# 130801_AriloRX_0_1.net
KiCad netlist of a schematic drawn in EAGLE
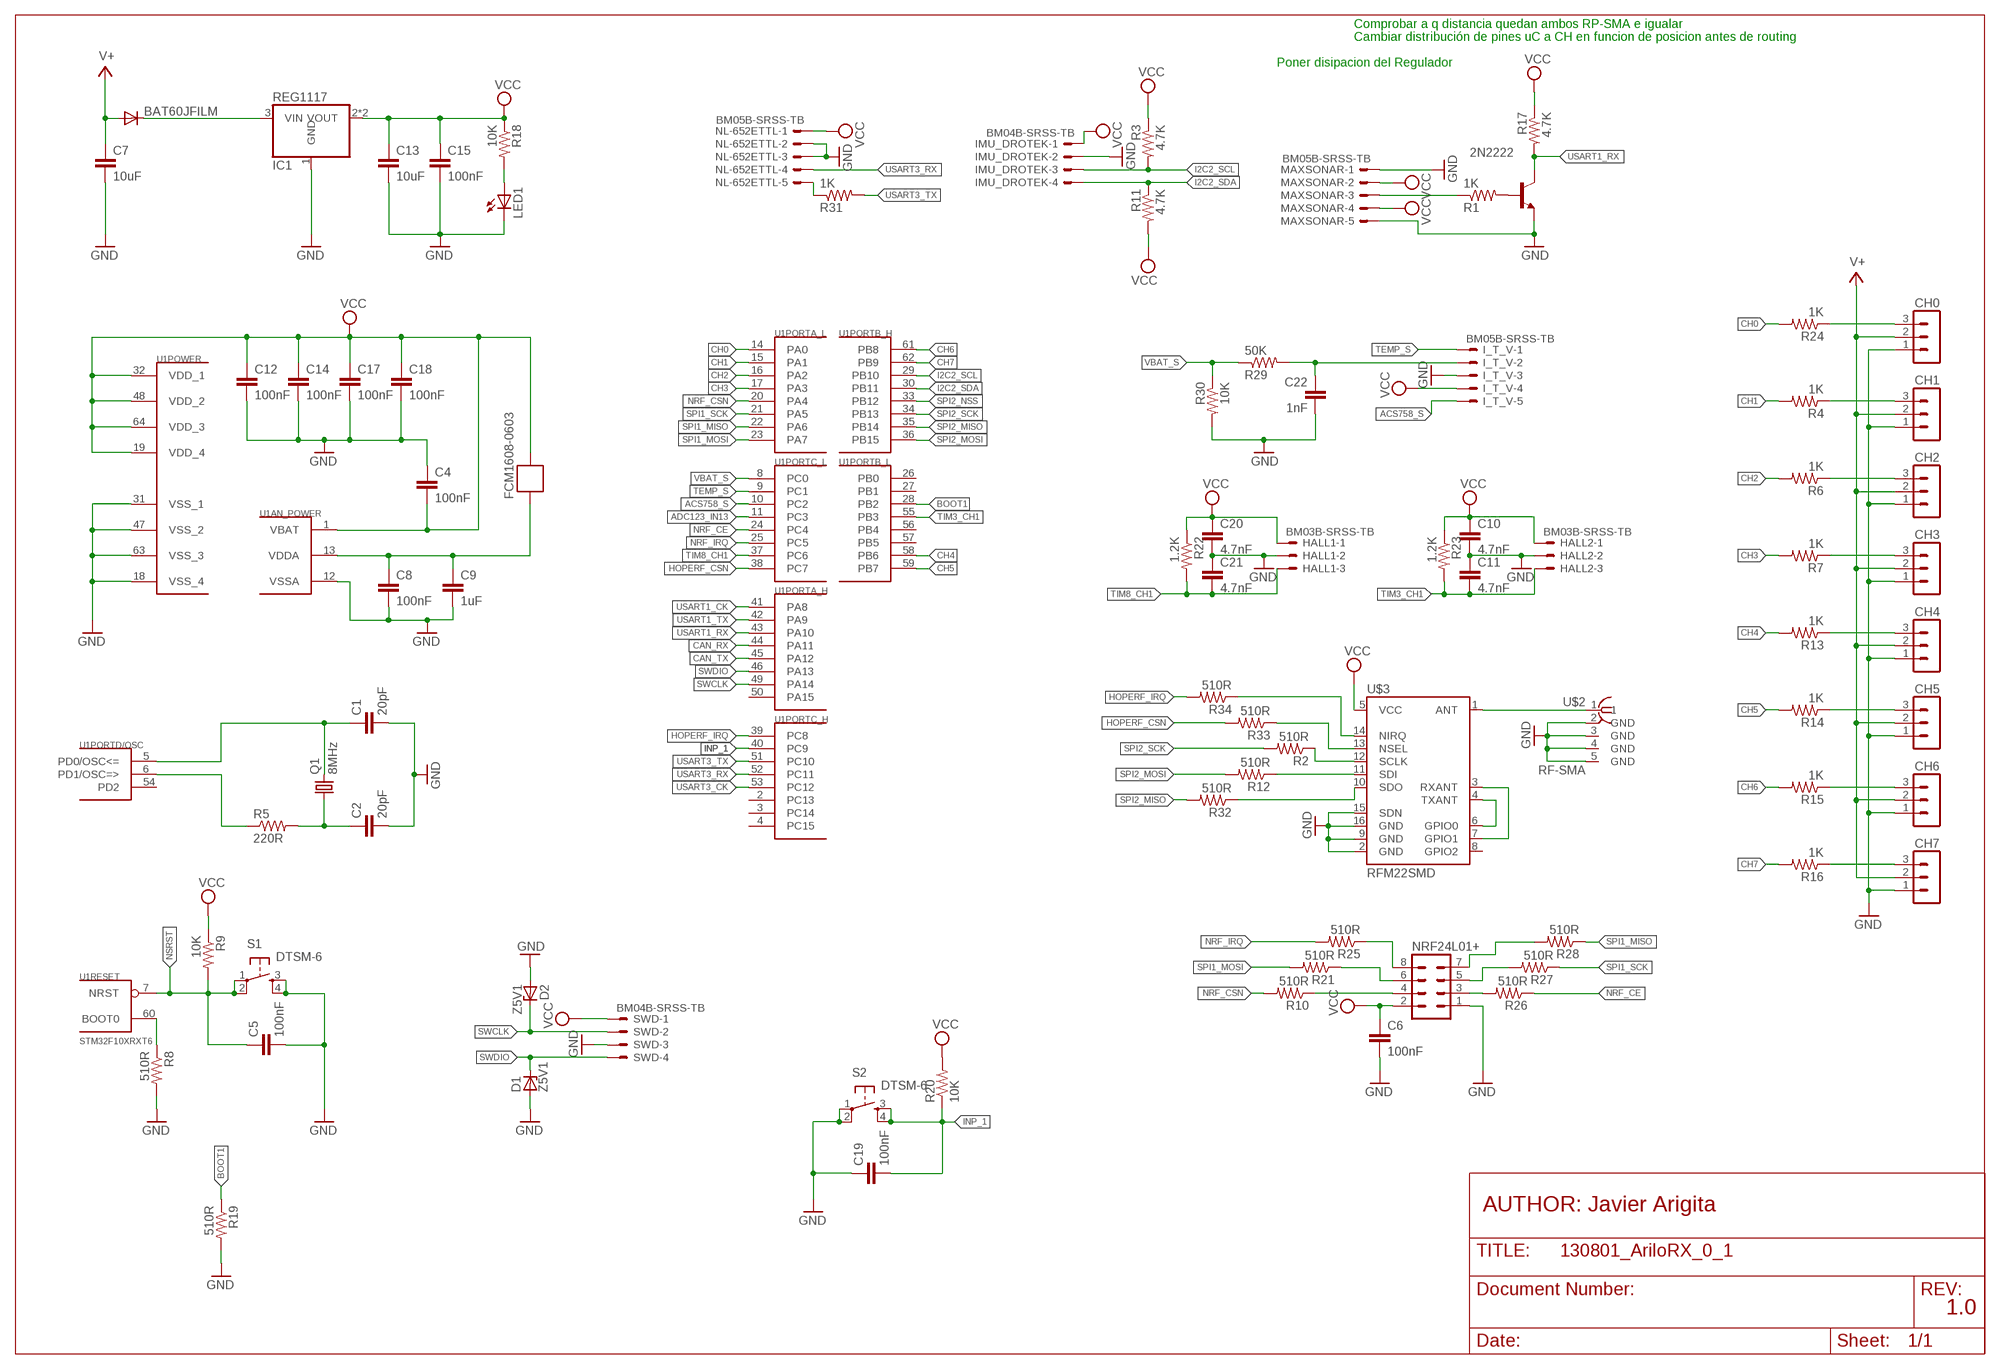
[diagram p0: schematic, sheet 1]

(export (version "E")
  (design (tool "Eeschema 10.0.6"))
  (components
    (comp (ref "2N2222")
      (value "MMBT2222ALT1-NPN-SOT23-BEC")
      (footprint "eagle-import:SOT23-BEC")
      (libsource (lib "eagle-import") (part "-NPN-SOT23-BECMMBT2222ALT1"))
    )
    (comp (ref "BAT60JFILM")
      (value "DIODE-SOD323-R")
      (footprint "eagle-import:SOD323-R")
      (libsource (lib "eagle-import") (part "DIODE-SOD323-R"))
    )
    (comp (ref "C1")
      (value "20pF")
      (footprint "eagle-import:C0805")
      (libsource (lib "eagle-import") (part "C-EUC0805"))
    )
    (comp (ref "C2")
      (value "20pF")
      (footprint "eagle-import:C0805")
      (libsource (lib "eagle-import") (part "C-EUC0805"))
    )
    (comp (ref "C4")
      (value "100nF")
      (footprint "eagle-import:C0805")
      (libsource (lib "eagle-import") (part "C-EUC0805"))
    )
    (comp (ref "C5")
      (value "100nF")
      (footprint "eagle-import:C0805")
      (libsource (lib "eagle-import") (part "C-EUC0805"))
    )
    (comp (ref "C6")
      (value "100nF")
      (footprint "eagle-import:C0805")
      (libsource (lib "eagle-import") (part "C-EUC0805"))
    )
    (comp (ref "C7")
      (value "10uF")
      (footprint "eagle-import:C3216")
      (libsource (lib "eagle-import") (part "resistor_C-EUC3216"))
    )
    (comp (ref "C8")
      (value "100nF")
      (footprint "eagle-import:C0805")
      (libsource (lib "eagle-import") (part "C-EUC0805"))
    )
    (comp (ref "C9")
      (value "1uF")
      (footprint "eagle-import:C3216")
      (libsource (lib "eagle-import") (part "resistor_C-EUC3216"))
    )
    (comp (ref "C10")
      (value "4.7nF")
      (footprint "eagle-import:C0805")
      (libsource (lib "eagle-import") (part "C-EUC0805"))
    )
    (comp (ref "C11")
      (value "4.7nF")
      (footprint "eagle-import:C0805")
      (libsource (lib "eagle-import") (part "C-EUC0805"))
    )
    (comp (ref "C12")
      (value "100nF")
      (footprint "eagle-import:C0805")
      (libsource (lib "eagle-import") (part "C-EUC0805"))
    )
    (comp (ref "C13")
      (value "10uF")
      (footprint "eagle-import:C3216")
      (libsource (lib "eagle-import") (part "resistor_C-EUC3216"))
    )
    (comp (ref "C14")
      (value "100nF")
      (footprint "eagle-import:C0805")
      (libsource (lib "eagle-import") (part "C-EUC0805"))
    )
    (comp (ref "C15")
      (value "100nF")
      (footprint "eagle-import:C0805")
      (libsource (lib "eagle-import") (part "C-EUC0805"))
    )
    (comp (ref "C17")
      (value "100nF")
      (footprint "eagle-import:C0805")
      (libsource (lib "eagle-import") (part "C-EUC0805"))
    )
    (comp (ref "C18")
      (value "100nF")
      (footprint "eagle-import:C0805")
      (libsource (lib "eagle-import") (part "C-EUC0805"))
    )
    (comp (ref "C19")
      (value "100nF")
      (footprint "eagle-import:C0805")
      (libsource (lib "eagle-import") (part "C-EUC0805"))
    )
    (comp (ref "C20")
      (value "4.7nF")
      (footprint "eagle-import:C0805")
      (libsource (lib "eagle-import") (part "C-EUC0805"))
    )
    (comp (ref "C21")
      (value "4.7nF")
      (footprint "eagle-import:C0805")
      (libsource (lib "eagle-import") (part "C-EUC0805"))
    )
    (comp (ref "C22")
      (value "1nF")
      (footprint "eagle-import:C0805")
      (libsource (lib "eagle-import") (part "C-EUC0805"))
    )
    (comp (ref "CH0")
      (value "MA03-1")
      (footprint "eagle-import:MA03-1")
      (libsource (lib "eagle-import") (part "MA03-1"))
    )
    (comp (ref "CH1")
      (value "MA03-1")
      (footprint "eagle-import:MA03-1")
      (libsource (lib "eagle-import") (part "MA03-1"))
    )
    (comp (ref "CH2")
      (value "MA03-1")
      (footprint "eagle-import:MA03-1")
      (libsource (lib "eagle-import") (part "MA03-1"))
    )
    (comp (ref "CH3")
      (value "MA03-1")
      (footprint "eagle-import:MA03-1")
      (libsource (lib "eagle-import") (part "MA03-1"))
    )
    (comp (ref "CH4")
      (value "MA03-1")
      (footprint "eagle-import:MA03-1")
      (libsource (lib "eagle-import") (part "MA03-1"))
    )
    (comp (ref "CH5")
      (value "MA03-1")
      (footprint "eagle-import:MA03-1")
      (libsource (lib "eagle-import") (part "MA03-1"))
    )
    (comp (ref "CH6")
      (value "MA03-1")
      (footprint "eagle-import:MA03-1")
      (libsource (lib "eagle-import") (part "MA03-1"))
    )
    (comp (ref "CH7")
      (value "MA03-1")
      (footprint "eagle-import:MA03-1")
      (libsource (lib "eagle-import") (part "MA03-1"))
    )
    (comp (ref "D1")
      (value "Z5V1")
      (footprint "eagle-import:SOD80C")
      (libsource (lib "eagle-import") (part "ZENER-DIODESOD80C"))
    )
    (comp (ref "D2")
      (value "Z5V1")
      (footprint "eagle-import:SOD80C")
      (libsource (lib "eagle-import") (part "ZENER-DIODESOD80C"))
    )
    (comp (ref "FCM1608-0603")
      (value "FERRITE-BEAD")
      (footprint "eagle-import:R0603")
      (libsource (lib "eagle-import") (part "FERRITE-BEAD"))
    )
    (comp (ref "HALL1")
      (value "BM03B-SRSS-TB")
      (footprint "eagle-import:BM03B-SRSS-TB")
      (libsource (lib "eagle-import") (part "?M03B-SRSS-TBB"))
    )
    (comp (ref "HALL2")
      (value "BM03B-SRSS-TB")
      (footprint "eagle-import:BM03B-SRSS-TB")
      (libsource (lib "eagle-import") (part "?M03B-SRSS-TBB"))
    )
    (comp (ref "IC1")
      (value "REG1117")
      (footprint "eagle-import:SOT223")
      (libsource (lib "eagle-import") (part "REG1117"))
    )
    (comp (ref "IMU_DROTEK")
      (value "BM04B-SRSS-TB")
      (footprint "eagle-import:BM04B-SRSS-TB")
      (libsource (lib "eagle-import") (part "?M04B-SRSS-TBB"))
    )
    (comp (ref "I_T_V")
      (value "BM05B-SRSS-TB")
      (footprint "eagle-import:BM05B-SRSS-TB")
      (libsource (lib "eagle-import") (part "?M05B-SRSS-TBB"))
    )
    (comp (ref "LED1")
      (value "LED0805")
      (footprint "eagle-import:CHIPLED_0805")
      (libsource (lib "eagle-import") (part "LED0805"))
    )
    (comp (ref "MAXSONAR")
      (value "BM05B-SRSS-TB")
      (footprint "eagle-import:BM05B-SRSS-TB")
      (libsource (lib "eagle-import") (part "?M05B-SRSS-TBB"))
    )
    (comp (ref "NL-652ETTL")
      (value "BM05B-SRSS-TB")
      (footprint "eagle-import:BM05B-SRSS-TB")
      (libsource (lib "eagle-import") (part "?M05B-SRSS-TBB"))
    )
    (comp (ref "NRF24L01+")
      (value "MA04-2")
      (footprint "eagle-import:MA04-2")
      (libsource (lib "eagle-import") (part "MA04-2"))
    )
    (comp (ref "Q1")
      (value "8MHz")
      (footprint "eagle-import:SM49")
      (libsource (lib "eagle-import") (part "CRYSTALSM49"))
    )
    (comp (ref "R1")
      (value "1K")
      (footprint "eagle-import:R0805")
      (libsource (lib "eagle-import") (part "RESISTOR0805"))
    )
    (comp (ref "R2")
      (value "510R")
      (footprint "eagle-import:R0805")
      (libsource (lib "eagle-import") (part "RESISTOR0805"))
    )
    (comp (ref "R3")
      (value "4.7K")
      (footprint "eagle-import:R0805")
      (libsource (lib "eagle-import") (part "RESISTOR0805"))
    )
    (comp (ref "R4")
      (value "1K")
      (footprint "eagle-import:R0805")
      (libsource (lib "eagle-import") (part "RESISTOR0805"))
    )
    (comp (ref "R5")
      (value "220R")
      (footprint "eagle-import:R0805")
      (libsource (lib "eagle-import") (part "RESISTOR0805"))
    )
    (comp (ref "R6")
      (value "1K")
      (footprint "eagle-import:R0805")
      (libsource (lib "eagle-import") (part "RESISTOR0805"))
    )
    (comp (ref "R7")
      (value "1K")
      (footprint "eagle-import:R0805")
      (libsource (lib "eagle-import") (part "RESISTOR0805"))
    )
    (comp (ref "R8")
      (value "510R")
      (footprint "eagle-import:R0805")
      (libsource (lib "eagle-import") (part "RESISTOR0805"))
    )
    (comp (ref "R9")
      (value "10K")
      (footprint "eagle-import:R0805")
      (libsource (lib "eagle-import") (part "RESISTOR0805"))
    )
    (comp (ref "R10")
      (value "510R")
      (footprint "eagle-import:R0805")
      (libsource (lib "eagle-import") (part "RESISTOR0805"))
    )
    (comp (ref "R11")
      (value "4.7K")
      (footprint "eagle-import:R0805")
      (libsource (lib "eagle-import") (part "RESISTOR0805"))
    )
    (comp (ref "R12")
      (value "510R")
      (footprint "eagle-import:R0805")
      (libsource (lib "eagle-import") (part "RESISTOR0805"))
    )
    (comp (ref "R13")
      (value "1K")
      (footprint "eagle-import:R0805")
      (libsource (lib "eagle-import") (part "RESISTOR0805"))
    )
    (comp (ref "R14")
      (value "1K")
      (footprint "eagle-import:R0805")
      (libsource (lib "eagle-import") (part "RESISTOR0805"))
    )
    (comp (ref "R15")
      (value "1K")
      (footprint "eagle-import:R0805")
      (libsource (lib "eagle-import") (part "RESISTOR0805"))
    )
    (comp (ref "R16")
      (value "1K")
      (footprint "eagle-import:R0805")
      (libsource (lib "eagle-import") (part "RESISTOR0805"))
    )
    (comp (ref "R17")
      (value "4.7K")
      (footprint "eagle-import:R0805")
      (libsource (lib "eagle-import") (part "RESISTOR0805"))
    )
    (comp (ref "R18")
      (value "10K")
      (footprint "eagle-import:R0805")
      (libsource (lib "eagle-import") (part "RESISTOR0805"))
    )
    (comp (ref "R19")
      (value "510R")
      (footprint "eagle-import:R0805")
      (libsource (lib "eagle-import") (part "RESISTOR0805"))
    )
    (comp (ref "R20")
      (value "10K")
      (footprint "eagle-import:R0805")
      (libsource (lib "eagle-import") (part "RESISTOR0805"))
    )
    (comp (ref "R21")
      (value "510R")
      (footprint "eagle-import:R0805")
      (libsource (lib "eagle-import") (part "RESISTOR0805"))
    )
    (comp (ref "R22")
      (value "1.2K")
      (footprint "eagle-import:R0805")
      (libsource (lib "eagle-import") (part "RESISTOR0805"))
    )
    (comp (ref "R23")
      (value "1.2K")
      (footprint "eagle-import:R0805")
      (libsource (lib "eagle-import") (part "RESISTOR0805"))
    )
    (comp (ref "R24")
      (value "1K")
      (footprint "eagle-import:R0805")
      (libsource (lib "eagle-import") (part "RESISTOR0805"))
    )
    (comp (ref "R25")
      (value "510R")
      (footprint "eagle-import:R0805")
      (libsource (lib "eagle-import") (part "RESISTOR0805"))
    )
    (comp (ref "R26")
      (value "510R")
      (footprint "eagle-import:R0805")
      (libsource (lib "eagle-import") (part "RESISTOR0805"))
    )
    (comp (ref "R27")
      (value "510R")
      (footprint "eagle-import:R0805")
      (libsource (lib "eagle-import") (part "RESISTOR0805"))
    )
    (comp (ref "R28")
      (value "510R")
      (footprint "eagle-import:R0805")
      (libsource (lib "eagle-import") (part "RESISTOR0805"))
    )
    (comp (ref "R29")
      (value "50K")
      (footprint "eagle-import:R0805")
      (libsource (lib "eagle-import") (part "RESISTOR0805"))
    )
    (comp (ref "R30")
      (value "10K")
      (footprint "eagle-import:R0805")
      (libsource (lib "eagle-import") (part "RESISTOR0805"))
    )
    (comp (ref "R31")
      (value "1K")
      (footprint "eagle-import:R0805")
      (libsource (lib "eagle-import") (part "RESISTOR0805"))
    )
    (comp (ref "R32")
      (value "510R")
      (footprint "eagle-import:R0805")
      (libsource (lib "eagle-import") (part "RESISTOR0805"))
    )
    (comp (ref "R33")
      (value "510R")
      (footprint "eagle-import:R0805")
      (libsource (lib "eagle-import") (part "RESISTOR0805"))
    )
    (comp (ref "R34")
      (value "510R")
      (footprint "eagle-import:R0805")
      (libsource (lib "eagle-import") (part "RESISTOR0805"))
    )
    (comp (ref "S1")
      (value "DTSM-6")
      (footprint "eagle-import:DTSM-6")
      (libsource (lib "eagle-import") (part "DTSM-6"))
    )
    (comp (ref "S2")
      (value "DTSM-6")
      (footprint "eagle-import:DTSM-6")
      (libsource (lib "eagle-import") (part "DTSM-6"))
    )
    (comp (ref "SWD")
      (value "BM04B-SRSS-TB")
      (footprint "eagle-import:BM04B-SRSS-TB")
      (libsource (lib "eagle-import") (part "?M04B-SRSS-TBB"))
    )
    (comp (ref "U$2")
      (value "RF-SMA")
      (footprint "eagle-import:BU-SMA-H")
      (libsource (lib "eagle-import") (part "RF-SMA"))
    )
    (comp (ref "U$3")
      (value "RFM22SMD")
      (footprint "eagle-import:RFM22-XXX-S2")
      (libsource (lib "eagle-import") (part "RFM22SMD"))
    )
    (comp (ref "U1")
      (value "STM32F10XRXT6")
      (footprint "eagle-import:TQFP64")
      (libsource (lib "eagle-import") (part "STM32F10XRXT6"))
    )
  )
  (nets
    (net (code "1") (name "ACS758_S") (class "Default")
      (node (ref "I_T_V") (pin "5") (pinfunction "S_5") (pintype "passive"))
      (node (ref "U1") (pin "10") (pinfunction "PC2_10") (pintype "bidirectional"))
    )
    (net (code "2") (name "ADC123_IN13") (class "Default")
      (node (ref "U1") (pin "11") (pinfunction "PC3_11") (pintype "bidirectional"))
    )
    (net (code "3") (name "BOOT1") (class "Default")
      (node (ref "R19") (pin "1") (pinfunction "1_1") (pintype "passive"))
      (node (ref "U1") (pin "28") (pinfunction "PB2_28") (pintype "bidirectional"))
    )
    (net (code "4") (name "CAN_RX") (class "Default")
      (node (ref "U1") (pin "44") (pinfunction "PA11_44") (pintype "bidirectional"))
    )
    (net (code "5") (name "CAN_TX") (class "Default")
      (node (ref "U1") (pin "45") (pinfunction "PA12_45") (pintype "bidirectional"))
    )
    (net (code "6") (name "CH0") (class "Default")
      (node (ref "R24") (pin "2") (pinfunction "2_2") (pintype "passive"))
      (node (ref "U1") (pin "14") (pinfunction "PA0_14") (pintype "bidirectional"))
    )
    (net (code "7") (name "CH1") (class "Default")
      (node (ref "R4") (pin "2") (pinfunction "2_2") (pintype "passive"))
      (node (ref "U1") (pin "15") (pinfunction "PA1_15") (pintype "bidirectional"))
    )
    (net (code "8") (name "CH2") (class "Default")
      (node (ref "R6") (pin "2") (pinfunction "2_2") (pintype "passive"))
      (node (ref "U1") (pin "16") (pinfunction "PA2_16") (pintype "bidirectional"))
    )
    (net (code "9") (name "CH3") (class "Default")
      (node (ref "R7") (pin "2") (pinfunction "2_2") (pintype "passive"))
      (node (ref "U1") (pin "17") (pinfunction "PA3_17") (pintype "bidirectional"))
    )
    (net (code "10") (name "CH4") (class "Default")
      (node (ref "R13") (pin "2") (pinfunction "2_2") (pintype "passive"))
      (node (ref "U1") (pin "58") (pinfunction "PB6_58") (pintype "bidirectional"))
    )
    (net (code "11") (name "CH5") (class "Default")
      (node (ref "R14") (pin "2") (pinfunction "2_2") (pintype "passive"))
      (node (ref "U1") (pin "59") (pinfunction "PB7_59") (pintype "bidirectional"))
    )
    (net (code "12") (name "CH6") (class "Default")
      (node (ref "R15") (pin "2") (pinfunction "2_2") (pintype "passive"))
      (node (ref "U1") (pin "61") (pinfunction "PB8_61") (pintype "bidirectional"))
    )
    (net (code "13") (name "CH7") (class "Default")
      (node (ref "R16") (pin "2") (pinfunction "2_2") (pintype "passive"))
      (node (ref "U1") (pin "62") (pinfunction "PB9_62") (pintype "bidirectional"))
    )
    (net (code "14") (name "GND") (class "Default")
      (node (ref "2N2222") (pin "E") (pinfunction "E_E") (pintype "passive"))
      (node (ref "C1") (pin "2") (pinfunction "2_2") (pintype "passive"))
      (node (ref "C10") (pin "2") (pinfunction "2_2") (pintype "passive"))
      (node (ref "C11") (pin "1") (pinfunction "1_1") (pintype "passive"))
      (node (ref "C12") (pin "2") (pinfunction "2_2") (pintype "passive"))
      (node (ref "C13") (pin "2") (pinfunction "2_2") (pintype "passive"))
      (node (ref "C14") (pin "2") (pinfunction "2_2") (pintype "passive"))
      (node (ref "C15") (pin "2") (pinfunction "2_2") (pintype "passive"))
      (node (ref "C17") (pin "2") (pinfunction "2_2") (pintype "passive"))
      (node (ref "C18") (pin "2") (pinfunction "2_2") (pintype "passive"))
      (node (ref "C19") (pin "1") (pinfunction "1_1") (pintype "passive"))
      (node (ref "C2") (pin "2") (pinfunction "2_2") (pintype "passive"))
      (node (ref "C20") (pin "2") (pinfunction "2_2") (pintype "passive"))
      (node (ref "C21") (pin "1") (pinfunction "1_1") (pintype "passive"))
      (node (ref "C22") (pin "2") (pinfunction "2_2") (pintype "passive"))
      (node (ref "C4") (pin "1") (pinfunction "1_1") (pintype "passive"))
      (node (ref "C5") (pin "2") (pinfunction "2_2") (pintype "passive"))
      (node (ref "C6") (pin "2") (pinfunction "2_2") (pintype "passive"))
      (node (ref "C7") (pin "2") (pinfunction "2_2") (pintype "passive"))
      (node (ref "C8") (pin "2") (pinfunction "2_2") (pintype "passive"))
      (node (ref "C9") (pin "2") (pinfunction "2_2") (pintype "passive"))
      (node (ref "CH0") (pin "1") (pinfunction "1_1") (pintype "passive"))
      (node (ref "CH1") (pin "1") (pinfunction "1_1") (pintype "passive"))
      (node (ref "CH2") (pin "1") (pinfunction "1_1") (pintype "passive"))
      (node (ref "CH3") (pin "1") (pinfunction "1_1") (pintype "passive"))
      (node (ref "CH4") (pin "1") (pinfunction "1_1") (pintype "passive"))
      (node (ref "CH5") (pin "1") (pinfunction "1_1") (pintype "passive"))
      (node (ref "CH6") (pin "1") (pinfunction "1_1") (pintype "passive"))
      (node (ref "CH7") (pin "1") (pinfunction "1_1") (pintype "passive"))
      (node (ref "D1") (pin "A") (pinfunction "A_A") (pintype "passive"))
      (node (ref "D2") (pin "A") (pinfunction "A_A") (pintype "passive"))
      (node (ref "HALL1") (pin "2") (pinfunction "S_2") (pintype "passive"))
      (node (ref "HALL2") (pin "2") (pinfunction "S_2") (pintype "passive"))
      (node (ref "IC1") (pin "1") (pinfunction "GND_1") (pintype "power_in"))
      (node (ref "IMU_DROTEK") (pin "2") (pinfunction "S_2") (pintype "passive"))
      (node (ref "I_T_V") (pin "3") (pinfunction "S_3") (pintype "passive"))
      (node (ref "LED1") (pin "C") (pinfunction "C_C") (pintype "passive"))
      (node (ref "MAXSONAR") (pin "1") (pinfunction "S_1") (pintype "passive"))
      (node (ref "MAXSONAR") (pin "5") (pinfunction "S_5") (pintype "passive"))
      (node (ref "NL-652ETTL") (pin "2") (pinfunction "S_2") (pintype "passive"))
      (node (ref "NL-652ETTL") (pin "3") (pinfunction "S_3") (pintype "passive"))
      (node (ref "NRF24L01+") (pin "1") (pinfunction "1_1") (pintype "passive"))
      (node (ref "R19") (pin "2") (pinfunction "2_2") (pintype "passive"))
      (node (ref "R30") (pin "2") (pinfunction "2_2") (pintype "passive"))
      (node (ref "R8") (pin "2") (pinfunction "2_2") (pintype "passive"))
      (node (ref "S1") (pin "3") (pinfunction "3_3") (pintype "passive"))
      (node (ref "S1") (pin "4") (pinfunction "4_4") (pintype "passive"))
      (node (ref "S2") (pin "1") (pinfunction "1_1") (pintype "passive"))
      (node (ref "S2") (pin "2") (pinfunction "2_2") (pintype "passive"))
      (node (ref "SWD") (pin "3") (pinfunction "S_3") (pintype "passive"))
      (node (ref "U$2") (pin "2") (pinfunction "GND_2") (pintype "power_in"))
      (node (ref "U$2") (pin "3") (pinfunction "GND_3") (pintype "bidirectional"))
      (node (ref "U$2") (pin "4") (pinfunction "GND_4") (pintype "bidirectional"))
      (node (ref "U$2") (pin "5") (pinfunction "GND_5") (pintype "bidirectional"))
      (node (ref "U$3") (pin "15") (pinfunction "SDN_15") (pintype "input"))
      (node (ref "U$3") (pin "16") (pinfunction "GND_16") (pintype "power_in"))
      (node (ref "U$3") (pin "2") (pinfunction "GND_2") (pintype "power_in"))
      (node (ref "U$3") (pin "9") (pinfunction "GND_9") (pintype "power_in"))
      (node (ref "U1") (pin "12") (pinfunction "VSSA_12") (pintype "power_in"))
      (node (ref "U1") (pin "18") (pinfunction "VSS_4_18") (pintype "power_in"))
      (node (ref "U1") (pin "31") (pinfunction "VSS_1_31") (pintype "power_in"))
      (node (ref "U1") (pin "47") (pinfunction "VSS_2_47") (pintype "power_in"))
      (node (ref "U1") (pin "63") (pinfunction "VSS_3_63") (pintype "power_in"))
    )
    (net (code "15") (name "HOPERF_CSN") (class "Default")
      (node (ref "R33") (pin "2") (pinfunction "2_2") (pintype "passive"))
      (node (ref "U1") (pin "38") (pinfunction "PC7_38") (pintype "bidirectional"))
    )
    (net (code "16") (name "HOPERF_IRQ") (class "Default")
      (node (ref "R34") (pin "2") (pinfunction "2_2") (pintype "passive"))
      (node (ref "U1") (pin "39") (pinfunction "PC8_39") (pintype "bidirectional"))
    )
    (net (code "17") (name "I2C2_SCL") (class "Default")
      (node (ref "IMU_DROTEK") (pin "3") (pinfunction "S_3") (pintype "passive"))
      (node (ref "R3") (pin "2") (pinfunction "2_2") (pintype "passive"))
      (node (ref "U1") (pin "29") (pinfunction "PB10_29") (pintype "bidirectional"))
    )
    (net (code "18") (name "I2C2_SDA") (class "Default")
      (node (ref "IMU_DROTEK") (pin "4") (pinfunction "S_4") (pintype "passive"))
      (node (ref "R11") (pin "1") (pinfunction "1_1") (pintype "passive"))
      (node (ref "U1") (pin "30") (pinfunction "PB11_30") (pintype "bidirectional"))
    )
    (net (code "19") (name "INP_1") (class "Default")
      (node (ref "C19") (pin "2") (pinfunction "2_2") (pintype "passive"))
      (node (ref "R20") (pin "1") (pinfunction "1_1") (pintype "passive"))
      (node (ref "S2") (pin "3") (pinfunction "3_3") (pintype "passive"))
      (node (ref "S2") (pin "4") (pinfunction "4_4") (pintype "passive"))
      (node (ref "U1") (pin "40") (pinfunction "PC9_40") (pintype "bidirectional"))
    )
    (net (code "20") (name "NRF_CE") (class "Default")
      (node (ref "R26") (pin "1") (pinfunction "1_1") (pintype "passive"))
      (node (ref "U1") (pin "24") (pinfunction "PC4_24") (pintype "bidirectional"))
    )
    (net (code "21") (name "NRF_CSN") (class "Default")
      (node (ref "R10") (pin "2") (pinfunction "2_2") (pintype "passive"))
      (node (ref "U1") (pin "20") (pinfunction "PA4_20") (pintype "bidirectional"))
    )
    (net (code "22") (name "NRF_IRQ") (class "Default")
      (node (ref "R25") (pin "2") (pinfunction "2_2") (pintype "passive"))
      (node (ref "U1") (pin "25") (pinfunction "PC5_25") (pintype "bidirectional"))
    )
    (net (code "23") (name "NSRST") (class "Default")
      (node (ref "C5") (pin "1") (pinfunction "1_1") (pintype "passive"))
      (node (ref "R9") (pin "2") (pinfunction "2_2") (pintype "passive"))
      (node (ref "S1") (pin "1") (pinfunction "1_1") (pintype "passive"))
      (node (ref "S1") (pin "2") (pinfunction "2_2") (pintype "passive"))
      (node (ref "U1") (pin "7") (pinfunction "NRST_7") (pintype "input"))
    )
    (net (code "24") (name "Net-(2N2222-PadB)") (class "Default")
      (node (ref "2N2222") (pin "B") (pinfunction "B_B") (pintype "passive"))
      (node (ref "R1") (pin "2") (pinfunction "2_2") (pintype "passive"))
    )
    (net (code "25") (name "Net-(C2-Pad1)") (class "Default")
      (node (ref "C2") (pin "1") (pinfunction "1_1") (pintype "passive"))
      (node (ref "Q1") (pin "1") (pinfunction "1_1") (pintype "passive"))
      (node (ref "R5") (pin "2") (pinfunction "2_2") (pintype "passive"))
    )
    (net (code "26") (name "Net-(CH0-Pad3)") (class "Default")
      (node (ref "CH0") (pin "3") (pinfunction "3_3") (pintype "passive"))
      (node (ref "R24") (pin "1") (pinfunction "1_1") (pintype "passive"))
    )
    (net (code "27") (name "Net-(CH1-Pad3)") (class "Default")
      (node (ref "CH1") (pin "3") (pinfunction "3_3") (pintype "passive"))
      (node (ref "R4") (pin "1") (pinfunction "1_1") (pintype "passive"))
    )
    (net (code "28") (name "Net-(CH2-Pad3)") (class "Default")
      (node (ref "CH2") (pin "3") (pinfunction "3_3") (pintype "passive"))
      (node (ref "R6") (pin "1") (pinfunction "1_1") (pintype "passive"))
    )
    (net (code "29") (name "Net-(CH3-Pad3)") (class "Default")
      (node (ref "CH3") (pin "3") (pinfunction "3_3") (pintype "passive"))
      (node (ref "R7") (pin "1") (pinfunction "1_1") (pintype "passive"))
    )
    (net (code "30") (name "Net-(CH4-Pad3)") (class "Default")
      (node (ref "CH4") (pin "3") (pinfunction "3_3") (pintype "passive"))
      (node (ref "R13") (pin "1") (pinfunction "1_1") (pintype "passive"))
    )
    (net (code "31") (name "Net-(CH5-Pad3)") (class "Default")
      (node (ref "CH5") (pin "3") (pinfunction "3_3") (pintype "passive"))
      (node (ref "R14") (pin "1") (pinfunction "1_1") (pintype "passive"))
    )
    (net (code "32") (name "Net-(CH6-Pad3)") (class "Default")
      (node (ref "CH6") (pin "3") (pinfunction "3_3") (pintype "passive"))
      (node (ref "R15") (pin "1") (pinfunction "1_1") (pintype "passive"))
    )
    (net (code "33") (name "Net-(CH7-Pad3)") (class "Default")
      (node (ref "CH7") (pin "3") (pinfunction "3_3") (pintype "passive"))
      (node (ref "R16") (pin "1") (pinfunction "1_1") (pintype "passive"))
    )
    (net (code "34") (name "Net-(FCM1608-0603-P$2)") (class "Default")
      (node (ref "C8") (pin "1") (pinfunction "1_1") (pintype "passive"))
      (node (ref "C9") (pin "1") (pinfunction "1_1") (pintype "passive"))
      (node (ref "FCM1608-0603") (pin "2") (pinfunction "P$2_2") (pintype "bidirectional"))
      (node (ref "U1") (pin "13") (pinfunction "VDDA_13") (pintype "power_in"))
    )
    (net (code "35") (name "Net-(IC1-VIN)") (class "Default")
      (node (ref "BAT60JFILM") (pin "C") (pinfunction "C_C") (pintype "passive"))
      (node (ref "IC1") (pin "3") (pinfunction "VIN_3") (pintype "input"))
    )
    (net (code "36") (name "Net-(I_T_VB-S)") (class "Default")
      (node (ref "C22") (pin "1") (pinfunction "1_1") (pintype "passive"))
      (node (ref "I_T_V") (pin "2") (pinfunction "S_2") (pintype "passive"))
      (node (ref "R29") (pin "2") (pinfunction "2_2") (pintype "passive"))
    )
    (net (code "37") (name "Net-(LED1-PadA)") (class "Default")
      (node (ref "LED1") (pin "A") (pinfunction "A_A") (pintype "passive"))
      (node (ref "R18") (pin "2") (pinfunction "2_2") (pintype "passive"))
    )
    (net (code "38") (name "Net-(MAXSONARC-S)") (class "Default")
      (node (ref "MAXSONAR") (pin "3") (pinfunction "S_3") (pintype "passive"))
      (node (ref "R1") (pin "1") (pinfunction "1_1") (pintype "passive"))
    )
    (net (code "39") (name "Net-(NL-652ETTLE-S)") (class "Default")
      (node (ref "NL-652ETTL") (pin "5") (pinfunction "S_5") (pintype "passive"))
      (node (ref "R31") (pin "1") (pinfunction "1_1") (pintype "passive"))
    )
    (net (code "40") (name "Net-(NRF24L01+-Pad3)") (class "Default")
      (node (ref "NRF24L01+") (pin "3") (pinfunction "3_3") (pintype "passive"))
      (node (ref "R26") (pin "2") (pinfunction "2_2") (pintype "passive"))
    )
    (net (code "41") (name "Net-(NRF24L01+-Pad4)") (class "Default")
      (node (ref "NRF24L01+") (pin "4") (pinfunction "4_4") (pintype "passive"))
      (node (ref "R10") (pin "1") (pinfunction "1_1") (pintype "passive"))
    )
    (net (code "42") (name "Net-(NRF24L01+-Pad5)") (class "Default")
      (node (ref "NRF24L01+") (pin "5") (pinfunction "5_5") (pintype "passive"))
      (node (ref "R27") (pin "2") (pinfunction "2_2") (pintype "passive"))
    )
    (net (code "43") (name "Net-(NRF24L01+-Pad6)") (class "Default")
      (node (ref "NRF24L01+") (pin "6") (pinfunction "6_6") (pintype "passive"))
      (node (ref "R21") (pin "1") (pinfunction "1_1") (pintype "passive"))
    )
    (net (code "44") (name "Net-(NRF24L01+-Pad7)") (class "Default")
      (node (ref "NRF24L01+") (pin "7") (pinfunction "7_7") (pintype "passive"))
      (node (ref "R28") (pin "2") (pinfunction "2_2") (pintype "passive"))
    )
    (net (code "45") (name "Net-(NRF24L01+-Pad8)") (class "Default")
      (node (ref "NRF24L01+") (pin "8") (pinfunction "8_8") (pintype "passive"))
      (node (ref "R25") (pin "1") (pinfunction "1_1") (pintype "passive"))
    )
    (net (code "46") (name "Net-(U$3-ANT)") (class "Default")
      (node (ref "U$2") (pin "1") (pinfunction "1_1") (pintype "passive"))
      (node (ref "U$3") (pin "1") (pinfunction "ANT_1") (pintype "bidirectional"))
    )
    (net (code "47") (name "Net-(U$3-GPIO0)") (class "Default")
      (node (ref "U$3") (pin "4") (pinfunction "TXANT_4") (pintype "input"))
      (node (ref "U$3") (pin "6") (pinfunction "GPIO0_6") (pintype "bidirectional"))
    )
    (net (code "48") (name "Net-(U$3-GPIO1)") (class "Default")
      (node (ref "U$3") (pin "3") (pinfunction "RXANT_3") (pintype "input"))
      (node (ref "U$3") (pin "7") (pinfunction "GPIO1_7") (pintype "bidirectional"))
    )
    (net (code "49") (name "Net-(U$3-NIRQ)") (class "Default")
      (node (ref "R34") (pin "1") (pinfunction "1_1") (pintype "passive"))
      (node (ref "U$3") (pin "14") (pinfunction "NIRQ_14") (pintype "output"))
    )
    (net (code "50") (name "Net-(U$3-NSEL)") (class "Default")
      (node (ref "R33") (pin "1") (pinfunction "1_1") (pintype "passive"))
      (node (ref "U$3") (pin "13") (pinfunction "NSEL_13") (pintype "input"))
    )
    (net (code "51") (name "Net-(U$3-SCLK)") (class "Default")
      (node (ref "R2") (pin "1") (pinfunction "1_1") (pintype "passive"))
      (node (ref "U$3") (pin "12") (pinfunction "SCLK_12") (pintype "input"))
    )
    (net (code "52") (name "Net-(U$3-SDI)") (class "Default")
      (node (ref "R12") (pin "1") (pinfunction "1_1") (pintype "passive"))
      (node (ref "U$3") (pin "11") (pinfunction "SDI_11") (pintype "input"))
    )
    (net (code "53") (name "Net-(U$3-SDO)") (class "Default")
      (node (ref "R32") (pin "1") (pinfunction "1_1") (pintype "passive"))
      (node (ref "U$3") (pin "10") (pinfunction "SDO_10") (pintype "output"))
    )
    (net (code "54") (name "Net-(U1H-PD0{slash}OSC<=)") (class "Default")
      (node (ref "C1") (pin "1") (pinfunction "1_1") (pintype "passive"))
      (node (ref "Q1") (pin "2") (pinfunction "2_2") (pintype "passive"))
      (node (ref "U1") (pin "5") (pinfunction "PD0/OSC<=_5") (pintype "bidirectional"))
    )
    (net (code "55") (name "Net-(U1H-PD1{slash}OSC=>)") (class "Default")
      (node (ref "R5") (pin "1") (pinfunction "1_1") (pintype "passive"))
      (node (ref "U1") (pin "6") (pinfunction "PD1/OSC=>_6") (pintype "bidirectional"))
    )
    (net (code "56") (name "Net-(U1J-BOOT0)") (class "Default")
      (node (ref "R8") (pin "1") (pinfunction "1_1") (pintype "passive"))
      (node (ref "U1") (pin "60") (pinfunction "BOOT0_60") (pintype "input"))
    )
    (net (code "57") (name "SPI1_MISO") (class "Default")
      (node (ref "R28") (pin "1") (pinfunction "1_1") (pintype "passive"))
      (node (ref "U1") (pin "22") (pinfunction "PA6_22") (pintype "bidirectional"))
    )
    (net (code "58") (name "SPI1_MOSI") (class "Default")
      (node (ref "R21") (pin "2") (pinfunction "2_2") (pintype "passive"))
      (node (ref "U1") (pin "23") (pinfunction "PA7_23") (pintype "bidirectional"))
    )
    (net (code "59") (name "SPI1_SCK") (class "Default")
      (node (ref "R27") (pin "1") (pinfunction "1_1") (pintype "passive"))
      (node (ref "U1") (pin "21") (pinfunction "PA5_21") (pintype "bidirectional"))
    )
    (net (code "60") (name "SPI2_MISO") (class "Default")
      (node (ref "R32") (pin "2") (pinfunction "2_2") (pintype "passive"))
      (node (ref "U1") (pin "35") (pinfunction "PB14_35") (pintype "bidirectional"))
    )
    (net (code "61") (name "SPI2_MOSI") (class "Default")
      (node (ref "R12") (pin "2") (pinfunction "2_2") (pintype "passive"))
      (node (ref "U1") (pin "36") (pinfunction "PB15_36") (pintype "bidirectional"))
    )
    (net (code "62") (name "SPI2_NSS") (class "Default")
      (node (ref "U1") (pin "33") (pinfunction "PB12_33") (pintype "bidirectional"))
    )
    (net (code "63") (name "SPI2_SCK") (class "Default")
      (node (ref "R2") (pin "2") (pinfunction "2_2") (pintype "passive"))
      (node (ref "U1") (pin "34") (pinfunction "PB13_34") (pintype "bidirectional"))
    )
    (net (code "64") (name "SWCLK") (class "Default")
      (node (ref "D2") (pin "C") (pinfunction "C_C") (pintype "passive"))
      (node (ref "SWD") (pin "2") (pinfunction "S_2") (pintype "passive"))
      (node (ref "U1") (pin "49") (pinfunction "PA14_49") (pintype "bidirectional"))
    )
    (net (code "65") (name "SWDIO") (class "Default")
      (node (ref "D1") (pin "C") (pinfunction "C_C") (pintype "passive"))
      (node (ref "SWD") (pin "4") (pinfunction "S_4") (pintype "passive"))
      (node (ref "U1") (pin "46") (pinfunction "PA13_46") (pintype "bidirectional"))
    )
    (net (code "66") (name "TEMP_S") (class "Default")
      (node (ref "I_T_V") (pin "1") (pinfunction "S_1") (pintype "passive"))
      (node (ref "U1") (pin "9") (pinfunction "PC1_9") (pintype "bidirectional"))
    )
    (net (code "67") (name "TIM3_CH1") (class "Default")
      (node (ref "C11") (pin "2") (pinfunction "2_2") (pintype "passive"))
      (node (ref "HALL2") (pin "3") (pinfunction "S_3") (pintype "passive"))
      (node (ref "R23") (pin "2") (pinfunction "2_2") (pintype "passive"))
      (node (ref "U1") (pin "55") (pinfunction "PB3_55") (pintype "bidirectional"))
    )
    (net (code "68") (name "TIM8_CH1") (class "Default")
      (node (ref "C21") (pin "2") (pinfunction "2_2") (pintype "passive"))
      (node (ref "HALL1") (pin "3") (pinfunction "S_3") (pintype "passive"))
      (node (ref "R22") (pin "2") (pinfunction "2_2") (pintype "passive"))
      (node (ref "U1") (pin "37") (pinfunction "PC6_37") (pintype "bidirectional"))
    )
    (net (code "69") (name "USART1_CK") (class "Default")
      (node (ref "U1") (pin "41") (pinfunction "PA8_41") (pintype "bidirectional"))
    )
    (net (code "70") (name "USART1_RX") (class "Default")
      (node (ref "2N2222") (pin "C") (pinfunction "C_C") (pintype "passive"))
      (node (ref "R17") (pin "2") (pinfunction "2_2") (pintype "passive"))
      (node (ref "U1") (pin "43") (pinfunction "PA10_43") (pintype "bidirectional"))
    )
    (net (code "71") (name "USART1_TX") (class "Default")
      (node (ref "U1") (pin "42") (pinfunction "PA9_42") (pintype "bidirectional"))
    )
    (net (code "72") (name "USART3_CK") (class "Default")
      (node (ref "U1") (pin "53") (pinfunction "PC12_53") (pintype "bidirectional"))
    )
    (net (code "73") (name "USART3_RX") (class "Default")
      (node (ref "NL-652ETTL") (pin "4") (pinfunction "S_4") (pintype "passive"))
      (node (ref "U1") (pin "52") (pinfunction "PC11_52") (pintype "bidirectional"))
    )
    (net (code "74") (name "USART3_TX") (class "Default")
      (node (ref "R31") (pin "2") (pinfunction "2_2") (pintype "passive"))
      (node (ref "U1") (pin "51") (pinfunction "PC10_51") (pintype "bidirectional"))
    )
    (net (code "75") (name "V+") (class "Default")
      (node (ref "BAT60JFILM") (pin "A") (pinfunction "A_A") (pintype "passive"))
      (node (ref "C7") (pin "1") (pinfunction "1_1") (pintype "passive"))
      (node (ref "CH0") (pin "2") (pinfunction "2_2") (pintype "passive"))
      (node (ref "CH1") (pin "2") (pinfunction "2_2") (pintype "passive"))
      (node (ref "CH2") (pin "2") (pinfunction "2_2") (pintype "passive"))
      (node (ref "CH3") (pin "2") (pinfunction "2_2") (pintype "passive"))
      (node (ref "CH4") (pin "2") (pinfunction "2_2") (pintype "passive"))
      (node (ref "CH5") (pin "2") (pinfunction "2_2") (pintype "passive"))
      (node (ref "CH6") (pin "2") (pinfunction "2_2") (pintype "passive"))
      (node (ref "CH7") (pin "2") (pinfunction "2_2") (pintype "passive"))
    )
    (net (code "76") (name "VBAT_S") (class "Default")
      (node (ref "R29") (pin "1") (pinfunction "1_1") (pintype "passive"))
      (node (ref "R30") (pin "1") (pinfunction "1_1") (pintype "passive"))
      (node (ref "U1") (pin "8") (pinfunction "PC0_8") (pintype "bidirectional"))
    )
    (net (code "77") (name "VCC") (class "Default")
      (node (ref "C10") (pin "1") (pinfunction "1_1") (pintype "passive"))
      (node (ref "C12") (pin "1") (pinfunction "1_1") (pintype "passive"))
      (node (ref "C13") (pin "1") (pinfunction "1_1") (pintype "passive"))
      (node (ref "C14") (pin "1") (pinfunction "1_1") (pintype "passive"))
      (node (ref "C15") (pin "1") (pinfunction "1_1") (pintype "passive"))
      (node (ref "C17") (pin "1") (pinfunction "1_1") (pintype "passive"))
      (node (ref "C18") (pin "1") (pinfunction "1_1") (pintype "passive"))
      (node (ref "C20") (pin "1") (pinfunction "1_1") (pintype "passive"))
      (node (ref "C4") (pin "2") (pinfunction "2_2") (pintype "passive"))
      (node (ref "C6") (pin "1") (pinfunction "1_1") (pintype "passive"))
      (node (ref "FCM1608-0603") (pin "1") (pinfunction "P$1_1") (pintype "bidirectional"))
      (node (ref "HALL1") (pin "1") (pinfunction "S_1") (pintype "passive"))
      (node (ref "HALL2") (pin "1") (pinfunction "S_1") (pintype "passive"))
      (node (ref "IC1") (pin "2") (pinfunction "VOUT_2") (pintype "power_in"))
      (node (ref "IC1") (pin "4") (pinfunction "VOUT_4") (pintype "power_in"))
      (node (ref "IMU_DROTEK") (pin "1") (pinfunction "S_1") (pintype "passive"))
      (node (ref "I_T_V") (pin "4") (pinfunction "S_4") (pintype "passive"))
      (node (ref "MAXSONAR") (pin "2") (pinfunction "S_2") (pintype "passive"))
      (node (ref "MAXSONAR") (pin "4") (pinfunction "S_4") (pintype "passive"))
      (node (ref "NL-652ETTL") (pin "1") (pinfunction "S_1") (pintype "passive"))
      (node (ref "NRF24L01+") (pin "2") (pinfunction "2_2") (pintype "passive"))
      (node (ref "R11") (pin "2") (pinfunction "2_2") (pintype "passive"))
      (node (ref "R17") (pin "1") (pinfunction "1_1") (pintype "passive"))
      (node (ref "R18") (pin "1") (pinfunction "1_1") (pintype "passive"))
      (node (ref "R20") (pin "2") (pinfunction "2_2") (pintype "passive"))
      (node (ref "R22") (pin "1") (pinfunction "1_1") (pintype "passive"))
      (node (ref "R23") (pin "1") (pinfunction "1_1") (pintype "passive"))
      (node (ref "R3") (pin "1") (pinfunction "1_1") (pintype "passive"))
      (node (ref "R9") (pin "1") (pinfunction "1_1") (pintype "passive"))
      (node (ref "SWD") (pin "1") (pinfunction "S_1") (pintype "passive"))
      (node (ref "U$3") (pin "5") (pinfunction "VCC_5") (pintype "bidirectional"))
      (node (ref "U1") (pin "1") (pinfunction "VBAT_1") (pintype "power_in"))
      (node (ref "U1") (pin "19") (pinfunction "VDD_4_19") (pintype "power_in"))
      (node (ref "U1") (pin "32") (pinfunction "VDD_1_32") (pintype "power_in"))
      (node (ref "U1") (pin "48") (pinfunction "VDD_2_48") (pintype "power_in"))
      (node (ref "U1") (pin "64") (pinfunction "VDD_3_64") (pintype "power_in"))
    )
    (net (code "78") (name "unconnected-(U$3-GPIO2-Pad8)") (class "Default")
      (node (ref "U$3") (pin "8") (pinfunction "GPIO2_8") (pintype "bidirectional"))
    )
    (net (code "79") (name "unconnected-(U1B-PA15-Pad50)") (class "Default")
      (node (ref "U1") (pin "50") (pinfunction "PA15_50") (pintype "bidirectional"))
    )
    (net (code "80") (name "unconnected-(U1E-PB0-Pad26)") (class "Default")
      (node (ref "U1") (pin "26") (pinfunction "PB0_26") (pintype "bidirectional"))
    )
    (net (code "81") (name "unconnected-(U1E-PB1-Pad27)") (class "Default")
      (node (ref "U1") (pin "27") (pinfunction "PB1_27") (pintype "bidirectional"))
    )
    (net (code "82") (name "unconnected-(U1E-PB4-Pad56)") (class "Default")
      (node (ref "U1") (pin "56") (pinfunction "PB4_56") (pintype "bidirectional"))
    )
    (net (code "83") (name "unconnected-(U1E-PB5-Pad57)") (class "Default")
      (node (ref "U1") (pin "57") (pinfunction "PB5_57") (pintype "bidirectional"))
    )
    (net (code "84") (name "unconnected-(U1F-PC13-Pad2)") (class "Default")
      (node (ref "U1") (pin "2") (pinfunction "PC13_2") (pintype "bidirectional"))
    )
    (net (code "85") (name "unconnected-(U1F-PC14-Pad3)") (class "Default")
      (node (ref "U1") (pin "3") (pinfunction "PC14_3") (pintype "bidirectional"))
    )
    (net (code "86") (name "unconnected-(U1F-PC15-Pad4)") (class "Default")
      (node (ref "U1") (pin "4") (pinfunction "PC15_4") (pintype "bidirectional"))
    )
    (net (code "87") (name "unconnected-(U1H-PD2-Pad54)") (class "Default")
      (node (ref "U1") (pin "54") (pinfunction "PD2_54") (pintype "bidirectional"))
    )
  )
)
